# AT32UC3B0256_Breakout.net
KiCad netlist of a schematic drawn in Altium Designer
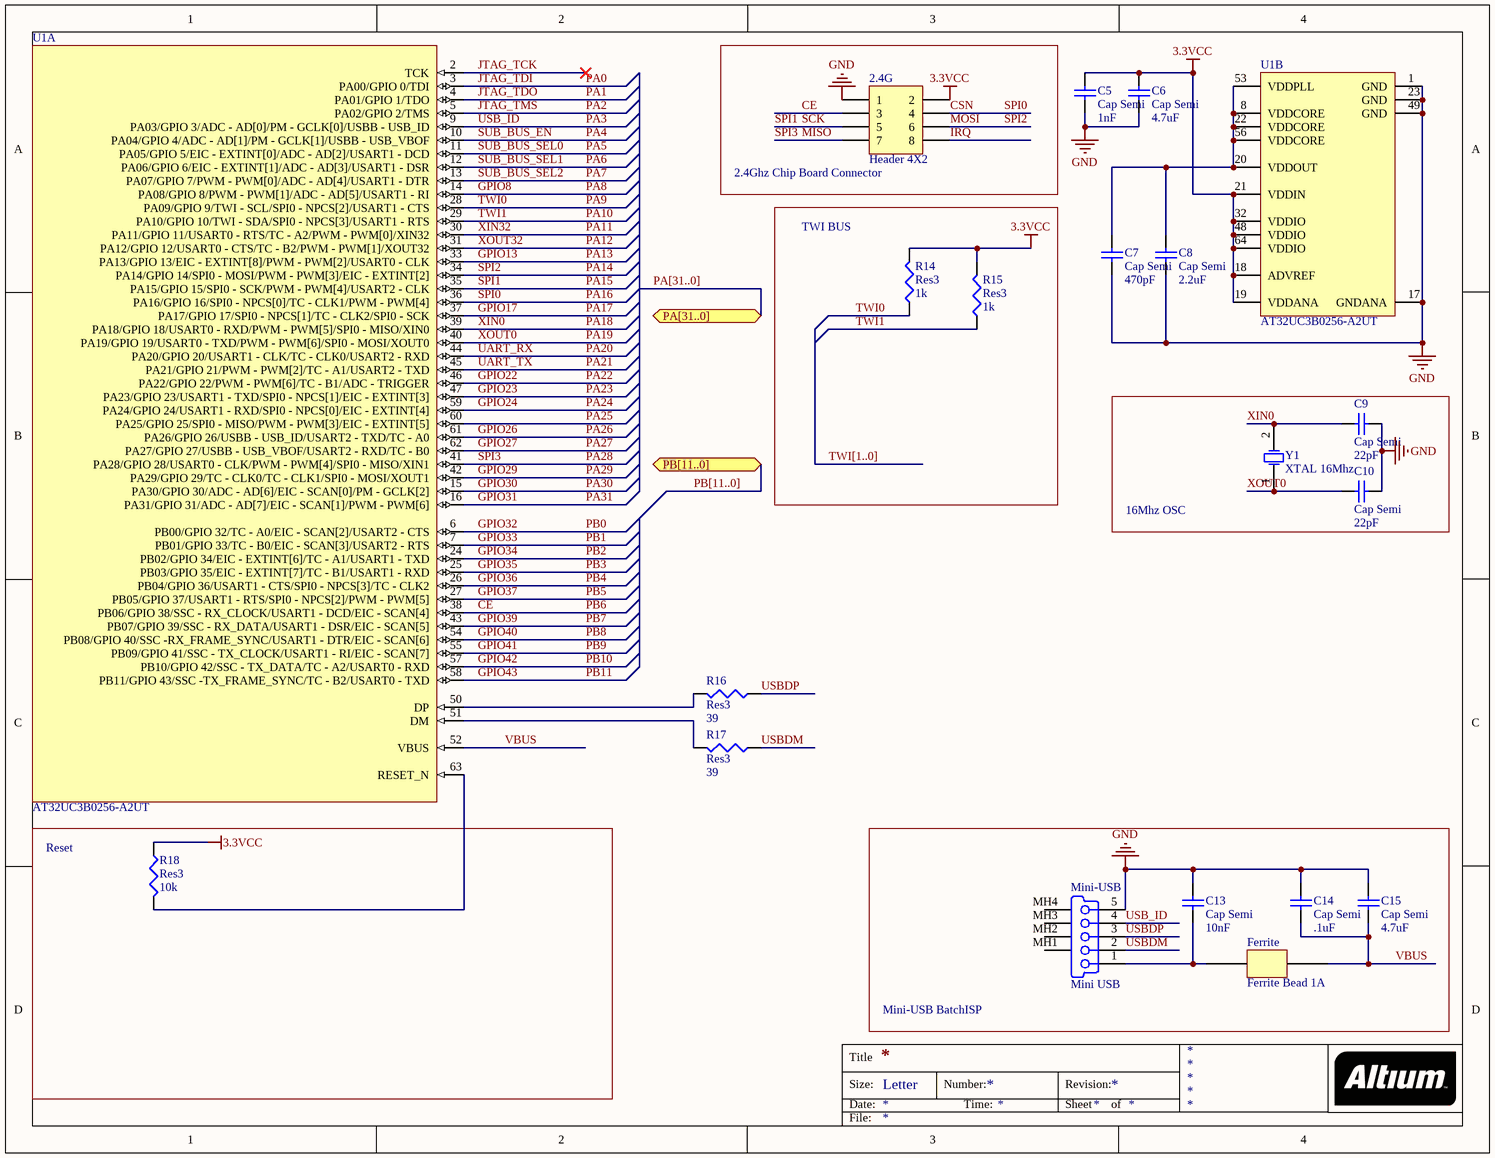
[diagram p0: AT32UC3B0256 Breakout.SchDoc]

(export (version "E")
  (design (tool "Eeschema 10.0.6"))
  (components
    (comp (ref "2.4G")
      (value "Header 4X2")
      (footprint "HDR2X4")
      (description "Header, 4-Pin, Dual row")
      (fields (field (name "PUBLISHER") "Altium Limited"))
      (libsource (lib "Miscellaneous Connectors") (part "Header 4X2"))
    )
    (comp (ref "C5")
      (value "Cap Semi")
      (footprint "CAPC2012L")
      (description "Capacitor (Semiconductor SIM Model)")
      (fields (field (name "ALTIUM_VALUE") "1nF") (field (name "PUBLISHER") "Altium Limited"))
      (libsource (lib "Miscellaneous Devices") (part "Cap Semi"))
    )
    (comp (ref "C6")
      (value "Cap Semi")
      (footprint "CAPC2012L")
      (description "Capacitor (Semiconductor SIM Model)")
      (fields (field (name "ALTIUM_VALUE") "4.7uF") (field (name "PUBLISHER") "Altium Limited"))
      (libsource (lib "Miscellaneous Devices") (part "Cap Semi"))
    )
    (comp (ref "C7")
      (value "Cap Semi")
      (footprint "CAPC2012L")
      (description "Capacitor (Semiconductor SIM Model)")
      (fields (field (name "ALTIUM_VALUE") "470pF") (field (name "PUBLISHER") "Altium Limited"))
      (libsource (lib "Miscellaneous Devices") (part "Cap Semi"))
    )
    (comp (ref "C8")
      (value "Cap Semi")
      (footprint "CAPC2012L")
      (description "Capacitor (Semiconductor SIM Model)")
      (fields (field (name "ALTIUM_VALUE") "2.2uF") (field (name "PUBLISHER") "Altium Limited"))
      (libsource (lib "Miscellaneous Devices") (part "Cap Semi"))
    )
    (comp (ref "C9")
      (value "Cap Semi")
      (footprint "CAPC2012L")
      (description "Capacitor (Semiconductor SIM Model)")
      (fields (field (name "ALTIUM_VALUE") "22pF") (field (name "PUBLISHER") "Altium Limited"))
      (libsource (lib "Miscellaneous Devices") (part "Cap Semi"))
    )
    (comp (ref "C10")
      (value "Cap Semi")
      (footprint "CAPC2012L")
      (description "Capacitor (Semiconductor SIM Model)")
      (fields (field (name "ALTIUM_VALUE") "22pF") (field (name "PUBLISHER") "Altium Limited"))
      (libsource (lib "Miscellaneous Devices") (part "Cap Semi"))
    )
    (comp (ref "C13")
      (value "Cap Semi")
      (footprint "CAPC2012L")
      (description "Capacitor (Semiconductor SIM Model)")
      (fields (field (name "ALTIUM_VALUE") "10nF") (field (name "PUBLISHER") "Altium Limited"))
      (libsource (lib "Miscellaneous Devices") (part "Cap Semi"))
    )
    (comp (ref "C14")
      (value "Cap Semi")
      (footprint "CAPC2012L")
      (description "Capacitor (Semiconductor SIM Model)")
      (fields (field (name "ALTIUM_VALUE") ".1uF") (field (name "PUBLISHER") "Altium Limited"))
      (libsource (lib "Miscellaneous Devices") (part "Cap Semi"))
    )
    (comp (ref "C15")
      (value "Cap Semi")
      (footprint "CAPC2012L")
      (description "Capacitor (Semiconductor SIM Model)")
      (fields (field (name "ALTIUM_VALUE") "4.7uF") (field (name "PUBLISHER") "Altium Limited"))
      (libsource (lib "Miscellaneous Devices") (part "Cap Semi"))
    )
    (comp (ref "Ferrite")
      (value "Ferrite Bead 1A")
      (footprint "C0805")
      (libsource (lib "Ferrite Bead") (part "Ferrite Bead"))
    )
    (comp (ref "Mini-USB")
      (value "Mini USB")
      (footprint "Mini USB")
      (libsource (lib "Mini USB") (part "Mini USB"))
    )
    (comp (ref "R14")
      (value "Res3")
      (footprint "C0805")
      (description "Resistor")
      (fields (field (name "ALTIUM_VALUE") "1k") (field (name "PUBLISHER") "Altium Limited"))
      (libsource (lib "Miscellaneous Devices") (part "Res3"))
    )
    (comp (ref "R15")
      (value "Res3")
      (footprint "C0805")
      (description "Resistor")
      (fields (field (name "ALTIUM_VALUE") "1k") (field (name "PUBLISHER") "Altium Limited"))
      (libsource (lib "Miscellaneous Devices") (part "Res3"))
    )
    (comp (ref "R16")
      (value "Res3")
      (footprint "C0805")
      (description "Resistor")
      (fields (field (name "ALTIUM_VALUE") "39") (field (name "PUBLISHER") "Altium Limited"))
      (libsource (lib "Miscellaneous Devices") (part "Res3"))
    )
    (comp (ref "R17")
      (value "Res3")
      (footprint "C0805")
      (description "Resistor")
      (fields (field (name "ALTIUM_VALUE") "39") (field (name "PUBLISHER") "Altium Limited"))
      (libsource (lib "Miscellaneous Devices") (part "Res3"))
    )
    (comp (ref "R18")
      (value "Res3")
      (footprint "C0805")
      (description "Resistor")
      (fields (field (name "ALTIUM_VALUE") "10k") (field (name "PUBLISHER") "Altium Limited"))
      (libsource (lib "Miscellaneous Devices") (part "Res3"))
    )
    (comp (ref "U1")
      (value "AT32UC3B0256-A2UT")
      (footprint "TQFP64_N")
      (fields (field (name "PUBLISHER") "Altium Limited"))
      (libsource (lib "Atmel Microcontroller 32-Bit AVR UC3") (part "AT32UC3B0256-A2UT"))
    )
    (comp (ref "Y1")
      (value "XTAL 16Mhz")
      (footprint "R38")
      (description "Crystal Oscillator")
      (fields (field (name "PUBLISHER") "Altium Limited"))
      (libsource (lib "Miscellaneous Devices") (part "XTAL"))
    )
  )
  (nets
    (net (code "1") (name "/IRQ") (class "Default")
      (node (ref "2.4G") (pin "8") (pinfunction "8_8") (pintype "passive"))
    )
    (net (code "2") (name "/JTAG_TCK") (class "Default")
      (node (ref "U1") (pin "2") (pinfunction "TCK_2") (pintype "input+no_connect"))
    )
    (net (code "3") (name "/PA0") (class "Default")
      (node (ref "U1") (pin "3") (pinfunction "PA00/GPIO_0/TDI_3") (pintype "bidirectional"))
    )
    (net (code "4") (name "/PA1") (class "Default")
      (node (ref "U1") (pin "4") (pinfunction "PA01/GPIO_1/TDO_4") (pintype "bidirectional"))
    )
    (net (code "5") (name "/PA2") (class "Default")
      (node (ref "U1") (pin "5") (pinfunction "PA02/GPIO_2/TMS_5") (pintype "bidirectional"))
    )
    (net (code "6") (name "/PA3") (class "Default")
      (node (ref "Mini-USB") (pin "4") (pinfunction "NC_4") (pintype "passive"))
      (node (ref "U1") (pin "9") (pinfunction "PA03/GPIO_3/ADC_-_AD[0]/PM_-_GCLK[0]/USBB_-_USB_ID_9") (pintype "bidirectional"))
    )
    (net (code "7") (name "/PA4") (class "Default")
      (node (ref "U1") (pin "10") (pinfunction "PA04/GPIO_4/ADC_-_AD[1]/PM_-_GCLK[1]/USBB_-_USB_VBOF_10") (pintype "bidirectional"))
    )
    (net (code "8") (name "/PA5") (class "Default")
      (node (ref "U1") (pin "11") (pinfunction "PA05/GPIO_5/EIC_-_EXTINT[0]/ADC_-_AD[2]/USART1_-_DCD_11") (pintype "bidirectional"))
    )
    (net (code "9") (name "/PA6") (class "Default")
      (node (ref "U1") (pin "12") (pinfunction "PA06/GPIO_6/EIC_-_EXTINT[1]/ADC_-_AD[3]/USART1_-_DSR_12") (pintype "bidirectional"))
    )
    (net (code "10") (name "/PA7") (class "Default")
      (node (ref "U1") (pin "13") (pinfunction "PA07/GPIO_7/PWM_-_PWM[0]/ADC_-_AD[4]/USART1_-_DTR_13") (pintype "bidirectional"))
    )
    (net (code "11") (name "/PA8") (class "Default")
      (node (ref "U1") (pin "14") (pinfunction "PA08/GPIO_8/PWM_-_PWM[1]/ADC_-_AD[5]/USART1_-_RI_14") (pintype "bidirectional"))
    )
    (net (code "12") (name "/PA11") (class "Default")
      (node (ref "U1") (pin "30") (pinfunction "PA11/GPIO_11/USART0_-_RTS/TC_-_A2/PWM_-_PWM[0]/XIN32_30") (pintype "bidirectional"))
    )
    (net (code "13") (name "/PA12") (class "Default")
      (node (ref "U1") (pin "31") (pinfunction "PA12/GPIO_12/USART0_-_CTS/TC_-_B2/PWM_-_PWM[1]/XOUT32_31") (pintype "bidirectional"))
    )
    (net (code "14") (name "/PA13") (class "Default")
      (node (ref "U1") (pin "33") (pinfunction "PA13/GPIO_13/EIC_-_EXTINT[8]/PWM_-_PWM[2]/USART0_-_CLK_33") (pintype "bidirectional"))
    )
    (net (code "15") (name "/PA14") (class "Default")
      (node (ref "2.4G") (pin "6") (pinfunction "6_6") (pintype "passive"))
      (node (ref "U1") (pin "34") (pinfunction "PA14/GPIO_14/SPI0_-_MOSI/PWM_-_PWM[3]/EIC_-_EXTINT[2]_34") (pintype "bidirectional"))
    )
    (net (code "16") (name "/PA15") (class "Default")
      (node (ref "2.4G") (pin "5") (pinfunction "5_5") (pintype "passive"))
      (node (ref "U1") (pin "35") (pinfunction "PA15/GPIO_15/SPI0_-_SCK/PWM_-_PWM[4]/USART2_-_CLK_35") (pintype "bidirectional"))
    )
    (net (code "17") (name "/PA16") (class "Default")
      (node (ref "2.4G") (pin "4") (pinfunction "4_4") (pintype "passive"))
      (node (ref "U1") (pin "36") (pinfunction "PA16/GPIO_16/SPI0_-_NPCS[0]/TC_-_CLK1/PWM_-_PWM[4]_36") (pintype "bidirectional"))
    )
    (net (code "18") (name "/PA17") (class "Default")
      (node (ref "U1") (pin "37") (pinfunction "PA17/GPIO_17/SPI0_-_NPCS[1]/TC_-_CLK2/SPI0_-_SCK_37") (pintype "bidirectional"))
    )
    (net (code "19") (name "/PA18") (class "Default")
      (node (ref "C9") (pin "2") (pinfunction "2_2") (pintype "passive"))
      (node (ref "U1") (pin "39") (pinfunction "PA18/GPIO_18/USART0_-_RXD/PWM_-_PWM[5]/SPI0_-_MISO/XIN0_39") (pintype "bidirectional"))
      (node (ref "Y1") (pin "2") (pinfunction "OSC2_2") (pintype "passive"))
    )
    (net (code "20") (name "/PA19") (class "Default")
      (node (ref "C10") (pin "2") (pinfunction "2_2") (pintype "passive"))
      (node (ref "U1") (pin "40") (pinfunction "PA19/GPIO_19/USART0_-_TXD/PWM_-_PWM[6]/SPI0_-_MOSI/XOUT0_40") (pintype "bidirectional"))
      (node (ref "Y1") (pin "1") (pinfunction "OSC1_1") (pintype "passive"))
    )
    (net (code "21") (name "/PA20") (class "Default")
      (node (ref "U1") (pin "44") (pinfunction "PA20/GPIO_20/USART1_-_CLK/TC_-_CLK0/USART2_-_RXD_44") (pintype "bidirectional"))
    )
    (net (code "22") (name "/PA21") (class "Default")
      (node (ref "U1") (pin "45") (pinfunction "PA21/GPIO_21/PWM_-_PWM[2]/TC_-_A1/USART2_-_TXD_45") (pintype "bidirectional"))
    )
    (net (code "23") (name "/PA22") (class "Default")
      (node (ref "U1") (pin "46") (pinfunction "PA22/GPIO_22/PWM_-_PWM[6]/TC_-_B1/ADC_-_TRIGGER_46") (pintype "bidirectional"))
    )
    (net (code "24") (name "/PA23") (class "Default")
      (node (ref "U1") (pin "47") (pinfunction "PA23/GPIO_23/USART1_-_TXD/SPI0_-_NPCS[1]/EIC_-_EXTINT[3]_47") (pintype "bidirectional"))
    )
    (net (code "25") (name "/PA24") (class "Default")
      (node (ref "U1") (pin "59") (pinfunction "PA24/GPIO_24/USART1_-_RXD/SPI0_-_NPCS[0]/EIC_-_EXTINT[4]_59") (pintype "bidirectional"))
    )
    (net (code "26") (name "/PA25") (class "Default")
      (node (ref "U1") (pin "60") (pinfunction "PA25/GPIO_25/SPI0_-_MISO/PWM_-_PWM[3]/EIC_-_EXTINT[5]_60") (pintype "bidirectional"))
    )
    (net (code "27") (name "/PA26") (class "Default")
      (node (ref "U1") (pin "61") (pinfunction "PA26/GPIO_26/USBB_-_USB_ID/USART2_-_TXD/TC_-_A0_61") (pintype "bidirectional"))
    )
    (net (code "28") (name "/PA27") (class "Default")
      (node (ref "U1") (pin "62") (pinfunction "PA27/GPIO_27/USBB_-_USB_VBOF/USART2_-_RXD/TC_-_B0_62") (pintype "bidirectional"))
    )
    (net (code "29") (name "/PA28") (class "Default")
      (node (ref "2.4G") (pin "7") (pinfunction "7_7") (pintype "passive"))
      (node (ref "U1") (pin "41") (pinfunction "PA28/GPIO_28/USART0_-_CLK/PWM_-_PWM[4]/SPI0_-_MISO/XIN1_41") (pintype "bidirectional"))
    )
    (net (code "30") (name "/PA29") (class "Default")
      (node (ref "U1") (pin "42") (pinfunction "PA29/GPIO_29/TC_-_CLK0/TC_-_CLK1/SPI0_-_MOSI/XOUT1_42") (pintype "bidirectional"))
    )
    (net (code "31") (name "/PA30") (class "Default")
      (node (ref "U1") (pin "15") (pinfunction "PA30/GPIO_30/ADC_-_AD[6]/EIC_-_SCAN[0]/PM_-_GCLK[2]_15") (pintype "bidirectional"))
    )
    (net (code "32") (name "/PA31") (class "Default")
      (node (ref "U1") (pin "16") (pinfunction "PA31/GPIO_31/ADC_-_AD[7]/EIC_-_SCAN[1]/PWM_-_PWM[6]_16") (pintype "bidirectional"))
    )
    (net (code "34") (name "/PB0") (class "Default")
      (node (ref "U1") (pin "6") (pinfunction "PB00/GPIO_32/TC_-_A0/EIC_-_SCAN[2]/USART2_-_CTS_6") (pintype "bidirectional"))
    )
    (net (code "35") (name "/PB1") (class "Default")
      (node (ref "U1") (pin "7") (pinfunction "PB01/GPIO_33/TC_-_B0/EIC_-_SCAN[3]/USART2_-_RTS_7") (pintype "bidirectional"))
    )
    (net (code "36") (name "/PB2") (class "Default")
      (node (ref "U1") (pin "24") (pinfunction "PB02/GPIO_34/EIC_-_EXTINT[6]/TC_-_A1/USART1_-_TXD_24") (pintype "bidirectional"))
    )
    (net (code "37") (name "/PB3") (class "Default")
      (node (ref "U1") (pin "25") (pinfunction "PB03/GPIO_35/EIC_-_EXTINT[7]/TC_-_B1/USART1_-_RXD_25") (pintype "bidirectional"))
    )
    (net (code "38") (name "/PB4") (class "Default")
      (node (ref "U1") (pin "26") (pinfunction "PB04/GPIO_36/USART1_-_CTS/SPI0_-_NPCS[3]/TC_-_CLK2_26") (pintype "bidirectional"))
    )
    (net (code "39") (name "/PB5") (class "Default")
      (node (ref "U1") (pin "27") (pinfunction "PB05/GPIO_37/USART1_-_RTS/SPI0_-_NPCS[2]/PWM_-_PWM[5]_27") (pintype "bidirectional"))
    )
    (net (code "40") (name "/PB6") (class "Default")
      (node (ref "2.4G") (pin "3") (pinfunction "3_3") (pintype "passive"))
      (node (ref "U1") (pin "38") (pinfunction "PB06/GPIO_38/SSC_-_RX_CLOCK/USART1_-_DCD/EIC_-_SCAN[4]_38") (pintype "bidirectional"))
    )
    (net (code "41") (name "/PB7") (class "Default")
      (node (ref "U1") (pin "43") (pinfunction "PB07/GPIO_39/SSC_-_RX_DATA/USART1_-_DSR/EIC_-_SCAN[5]_43") (pintype "bidirectional"))
    )
    (net (code "42") (name "/PB8") (class "Default")
      (node (ref "U1") (pin "54") (pinfunction "PB08/GPIO_40/SSC_-RX_FRAME_SYNC/USART1_-_DTR/EIC_-_SCAN[6]_54") (pintype "bidirectional"))
    )
    (net (code "43") (name "/PB9") (class "Default")
      (node (ref "U1") (pin "55") (pinfunction "PB09/GPIO_41/SSC_-_TX_CLOCK/USART1_-_RI/EIC_-_SCAN[7]_55") (pintype "bidirectional"))
    )
    (net (code "44") (name "/PB10") (class "Default")
      (node (ref "U1") (pin "57") (pinfunction "PB10/GPIO_42/SSC_-_TX_DATA/TC_-_A2/USART0_-_RXD_57") (pintype "bidirectional"))
    )
    (net (code "45") (name "/PB11") (class "Default")
      (node (ref "U1") (pin "58") (pinfunction "PB11/GPIO_43/SSC_-TX_FRAME_SYNC/TC_-_B2/USART0_-_TXD_58") (pintype "bidirectional"))
    )
    (net (code "47") (name "/TWI0") (class "Default")
      (node (ref "R14") (pin "1") (pinfunction "1_1") (pintype "passive"))
      (node (ref "U1") (pin "28") (pinfunction "PA09/GPIO_9/TWI_-_SCL/SPI0_-_NPCS[2]/USART1_-_CTS_28") (pintype "bidirectional"))
    )
    (net (code "48") (name "/TWI1") (class "Default")
      (node (ref "R15") (pin "1") (pinfunction "1_1") (pintype "passive"))
      (node (ref "U1") (pin "29") (pinfunction "PA10/GPIO_10/TWI_-_SDA/SPI0_-_NPCS[3]/USART1_-_RTS_29") (pintype "bidirectional"))
    )
    (net (code "50") (name "/USBDM") (class "Default")
      (node (ref "Mini-USB") (pin "2") (pinfunction "D-_2") (pintype "passive"))
      (node (ref "R17") (pin "1") (pinfunction "1_1") (pintype "passive"))
    )
    (net (code "51") (name "/USBDP") (class "Default")
      (node (ref "Mini-USB") (pin "3") (pinfunction "D+_3") (pintype "passive"))
      (node (ref "R16") (pin "1") (pinfunction "1_1") (pintype "passive"))
    )
    (net (code "52") (name "/VBUS") (class "Default")
      (node (ref "C14") (pin "1") (pinfunction "1_1") (pintype "passive"))
      (node (ref "C15") (pin "1") (pinfunction "1_1") (pintype "passive"))
      (node (ref "Ferrite") (pin "2") (pinfunction "2_2") (pintype "passive"))
      (node (ref "U1") (pin "52") (pinfunction "VBUS_52") (pintype "input"))
    )
    (net (code "53") (name "3.3VCC") (class "Default")
      (node (ref "2.4G") (pin "2") (pinfunction "2_2") (pintype "passive"))
      (node (ref "C5") (pin "2") (pinfunction "2_2") (pintype "passive"))
      (node (ref "C6") (pin "2") (pinfunction "2_2") (pintype "passive"))
      (node (ref "R14") (pin "2") (pinfunction "2_2") (pintype "passive"))
      (node (ref "R15") (pin "2") (pinfunction "2_2") (pintype "passive"))
      (node (ref "R18") (pin "1") (pinfunction "1_1") (pintype "passive"))
      (node (ref "U1") (pin "18") (pinfunction "ADVREF_18") (pintype "power_in"))
      (node (ref "U1") (pin "19") (pinfunction "VDDANA_19") (pintype "power_in"))
      (node (ref "U1") (pin "21") (pinfunction "VDDIN_21") (pintype "power_in"))
      (node (ref "U1") (pin "32") (pinfunction "VDDIO_32") (pintype "power_in"))
      (node (ref "U1") (pin "48") (pinfunction "VDDIO_48") (pintype "power_in"))
      (node (ref "U1") (pin "64") (pinfunction "VDDIO_64") (pintype "power_in"))
    )
    (net (code "54") (name "GND") (class "Default")
      (node (ref "2.4G") (pin "1") (pinfunction "1_1") (pintype "passive"))
      (node (ref "C10") (pin "1") (pinfunction "1_1") (pintype "passive"))
      (node (ref "C13") (pin "2") (pinfunction "2_2") (pintype "passive"))
      (node (ref "C14") (pin "2") (pinfunction "2_2") (pintype "passive"))
      (node (ref "C15") (pin "2") (pinfunction "2_2") (pintype "passive"))
      (node (ref "C5") (pin "1") (pinfunction "1_1") (pintype "passive"))
      (node (ref "C6") (pin "1") (pinfunction "1_1") (pintype "passive"))
      (node (ref "C7") (pin "1") (pinfunction "1_1") (pintype "passive"))
      (node (ref "C8") (pin "1") (pinfunction "1_1") (pintype "passive"))
      (node (ref "C9") (pin "1") (pinfunction "1_1") (pintype "passive"))
      (node (ref "Mini-USB") (pin "5") (pinfunction "GND_5") (pintype "passive"))
      (node (ref "U1") (pin "1") (pinfunction "GND_1") (pintype "power_in"))
      (node (ref "U1") (pin "17") (pinfunction "GNDANA_17") (pintype "power_in"))
      (node (ref "U1") (pin "23") (pinfunction "GND_23") (pintype "power_in"))
      (node (ref "U1") (pin "49") (pinfunction "GND_49") (pintype "power_in"))
    )
    (net (code "55") (name "Net-(Mini-USB-V_BUS_(5V))") (class "Default")
      (node (ref "C13") (pin "1") (pinfunction "1_1") (pintype "passive"))
      (node (ref "Ferrite") (pin "1") (pinfunction "1_1") (pintype "passive"))
      (node (ref "Mini-USB") (pin "1") (pinfunction "V_BUS_(5V)_1") (pintype "passive"))
    )
    (net (code "56") (name "Net-(U1A-DM)") (class "Default")
      (node (ref "R17") (pin "2") (pinfunction "2_2") (pintype "passive"))
      (node (ref "U1") (pin "51") (pinfunction "DM_51") (pintype "input"))
    )
    (net (code "57") (name "Net-(U1A-DP)") (class "Default")
      (node (ref "R16") (pin "2") (pinfunction "2_2") (pintype "passive"))
      (node (ref "U1") (pin "50") (pinfunction "DP_50") (pintype "input"))
    )
    (net (code "58") (name "Net-(U1A-RESET_N)") (class "Default")
      (node (ref "R18") (pin "2") (pinfunction "2_2") (pintype "passive"))
      (node (ref "U1") (pin "63") (pinfunction "RESET_N_63") (pintype "input"))
    )
    (net (code "59") (name "Net-(U1B-VDDOUT)") (class "Default")
      (node (ref "C7") (pin "2") (pinfunction "2_2") (pintype "passive"))
      (node (ref "C8") (pin "2") (pinfunction "2_2") (pintype "passive"))
      (node (ref "U1") (pin "20") (pinfunction "VDDOUT_20") (pintype "power_in"))
      (node (ref "U1") (pin "22") (pinfunction "VDDCORE_22") (pintype "power_in"))
      (node (ref "U1") (pin "53") (pinfunction "VDDPLL_53") (pintype "power_in"))
      (node (ref "U1") (pin "56") (pinfunction "VDDCORE_56") (pintype "power_in"))
      (node (ref "U1") (pin "8") (pinfunction "VDDCORE_8") (pintype "power_in"))
    )
    (net (code "60") (name "unconnected-(Mini-USB-Tab-PadMH1)") (class "Default")
      (node (ref "Mini-USB") (pin "MH1") (pinfunction "Tab_MH1") (pintype "passive"))
    )
    (net (code "61") (name "unconnected-(Mini-USB-Tab-PadMH2)") (class "Default")
      (node (ref "Mini-USB") (pin "MH2") (pinfunction "Tab_MH2") (pintype "passive"))
    )
    (net (code "62") (name "unconnected-(Mini-USB-Tab-PadMH3)") (class "Default")
      (node (ref "Mini-USB") (pin "MH3") (pinfunction "Tab_MH3") (pintype "passive"))
    )
    (net (code "63") (name "unconnected-(Mini-USB-Tab-PadMH4)") (class "Default")
      (node (ref "Mini-USB") (pin "MH4") (pinfunction "Tab_MH4") (pintype "passive"))
    )
  )
)
